# display.net
KiCad netlist of a schematic drawn in EAGLE
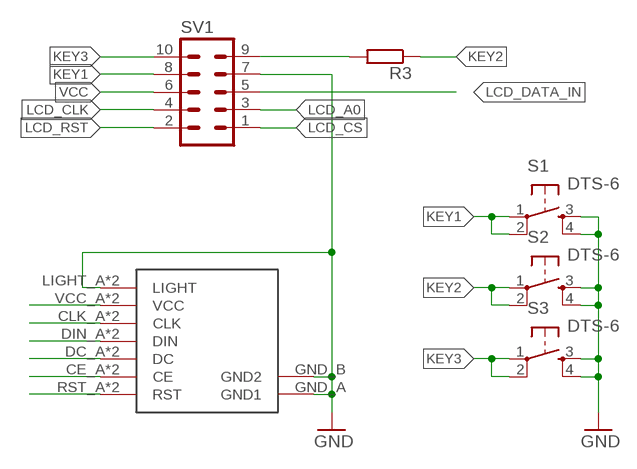
[diagram p0: schematic, sheet 1]

(export (version "E")
  (design (tool "Eeschema 10.0.6"))
  (components
    (comp (ref "R3")
      (value "R-EU_R2010")
      (footprint "eagle-import:R2010")
      (libsource (lib "eagle-import") (part "R-EU_R2010"))
    )
    (comp (ref "S1")
      (value "DTS-6")
      (footprint "eagle-import:DTS-6")
      (libsource (lib "eagle-import") (part "DTS-6"))
    )
    (comp (ref "S2")
      (value "DTS-6")
      (footprint "eagle-import:DTS-6")
      (libsource (lib "eagle-import") (part "DTS-6"))
    )
    (comp (ref "S3")
      (value "DTS-6")
      (footprint "eagle-import:DTS-6")
      (libsource (lib "eagle-import") (part "DTS-6"))
    )
    (comp (ref "SV1")
      (value "ML10L")
      (footprint "eagle-import:ML10L")
      (libsource (lib "eagle-import") (part "ML10L"))
    )
    (comp (ref "U$2")
      (value "NOKIA5110_LCD")
      (footprint "eagle-import:NOKIA5110_LCD")
      (libsource (lib "eagle-import") (part "NOKIA5110_LCD"))
    )
  )
  (nets
    (net (code "1") (name "GND") (class "Default")
      (node (ref "S1") (pin "3") (pinfunction "3_3") (pintype "passive"))
      (node (ref "S1") (pin "4") (pinfunction "4_4") (pintype "passive"))
      (node (ref "S2") (pin "3") (pinfunction "3_3") (pintype "passive"))
      (node (ref "S2") (pin "4") (pinfunction "4_4") (pintype "passive"))
      (node (ref "S3") (pin "3") (pinfunction "3_3") (pintype "passive"))
      (node (ref "S3") (pin "4") (pinfunction "4_4") (pintype "passive"))
      (node (ref "SV1") (pin "7") (pinfunction "7_7") (pintype "passive"))
      (node (ref "U$2") (pin "GND_A") (pinfunction "GND1_GND_A") (pintype "bidirectional"))
      (node (ref "U$2") (pin "GND_B") (pinfunction "GND2_GND_B") (pintype "bidirectional"))
      (node (ref "U$2") (pin "LIGHT_A") (pinfunction "LIGHT_LIGHT_A") (pintype "bidirectional"))
      (node (ref "U$2") (pin "LIGHT_B") (pinfunction "LIGHT_LIGHT_B") (pintype "bidirectional"))
    )
    (net (code "2") (name "KEY1") (class "Default")
      (node (ref "S1") (pin "1") (pinfunction "1_1") (pintype "passive"))
      (node (ref "S1") (pin "2") (pinfunction "2_2") (pintype "passive"))
      (node (ref "SV1") (pin "8") (pinfunction "8_8") (pintype "passive"))
    )
    (net (code "3") (name "KEY2") (class "Default")
      (node (ref "R3") (pin "1") (pinfunction "1_1") (pintype "passive"))
      (node (ref "S2") (pin "1") (pinfunction "1_1") (pintype "passive"))
      (node (ref "S2") (pin "2") (pinfunction "2_2") (pintype "passive"))
    )
    (net (code "4") (name "KEY3") (class "Default")
      (node (ref "S3") (pin "1") (pinfunction "1_1") (pintype "passive"))
      (node (ref "S3") (pin "2") (pinfunction "2_2") (pintype "passive"))
      (node (ref "SV1") (pin "10") (pinfunction "10_10") (pintype "passive"))
    )
    (net (code "5") (name "LCD_A0") (class "Default")
      (node (ref "SV1") (pin "3") (pinfunction "3_3") (pintype "passive"))
      (node (ref "U$2") (pin "DC_A") (pinfunction "DC_DC_A") (pintype "bidirectional"))
      (node (ref "U$2") (pin "DC_B") (pinfunction "DC_DC_B") (pintype "bidirectional"))
    )
    (net (code "6") (name "LCD_CLK") (class "Default")
      (node (ref "SV1") (pin "4") (pinfunction "4_4") (pintype "passive"))
      (node (ref "U$2") (pin "CLK_A") (pinfunction "CLK_CLK_A") (pintype "bidirectional"))
      (node (ref "U$2") (pin "CLK_B") (pinfunction "CLK_CLK_B") (pintype "bidirectional"))
    )
    (net (code "7") (name "LCD_CS") (class "Default")
      (node (ref "SV1") (pin "1") (pinfunction "1_1") (pintype "passive"))
      (node (ref "U$2") (pin "CE_A") (pinfunction "CE_CE_A") (pintype "bidirectional"))
      (node (ref "U$2") (pin "CE_B") (pinfunction "CE_CE_B") (pintype "bidirectional"))
    )
    (net (code "8") (name "LCD_DATA_IN") (class "Default")
      (node (ref "SV1") (pin "5") (pinfunction "5_5") (pintype "passive"))
      (node (ref "U$2") (pin "DIN_A") (pinfunction "DIN_DIN_A") (pintype "bidirectional"))
      (node (ref "U$2") (pin "DIN_B") (pinfunction "DIN_DIN_B") (pintype "bidirectional"))
    )
    (net (code "9") (name "LCD_RST") (class "Default")
      (node (ref "SV1") (pin "2") (pinfunction "2_2") (pintype "passive"))
      (node (ref "U$2") (pin "RST_A") (pinfunction "RST_RST_A") (pintype "bidirectional"))
      (node (ref "U$2") (pin "RST_B") (pinfunction "RST_RST_B") (pintype "bidirectional"))
    )
    (net (code "10") (name "Net-(R3-Pad2)") (class "Default")
      (node (ref "R3") (pin "2") (pinfunction "2_2") (pintype "passive"))
      (node (ref "SV1") (pin "9") (pinfunction "9_9") (pintype "passive"))
    )
    (net (code "11") (name "VCC") (class "Default")
      (node (ref "SV1") (pin "6") (pinfunction "6_6") (pintype "passive"))
      (node (ref "U$2") (pin "VCC_A") (pinfunction "VCC_VCC_A") (pintype "bidirectional"))
      (node (ref "U$2") (pin "VCC_B") (pinfunction "VCC_VCC_B") (pintype "bidirectional"))
    )
  )
)
